# raspdancer11_1_0.net
KiCad netlist of a schematic drawn in EAGLE
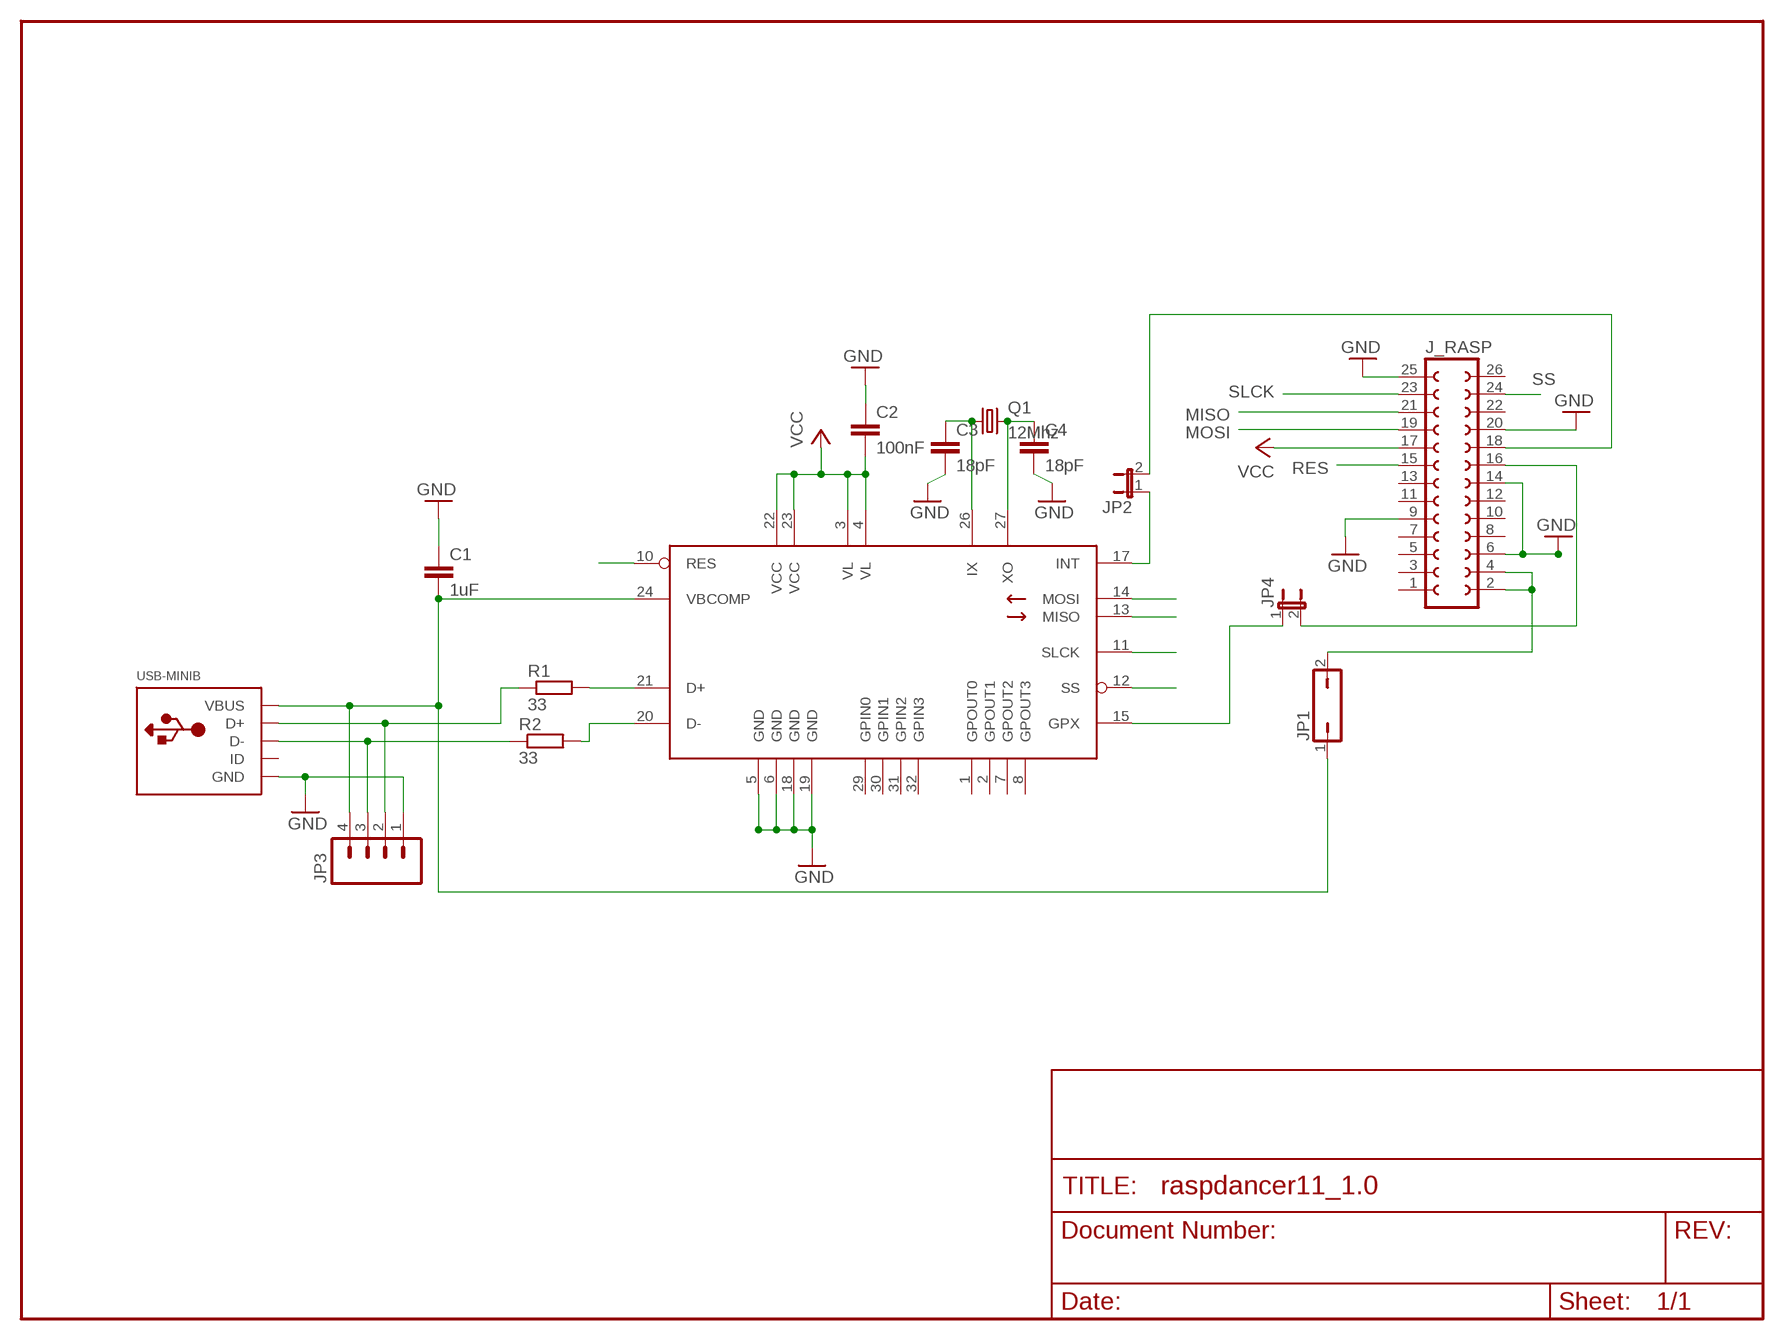
[diagram p0: schematic, sheet 1]

(export (version "E")
  (design (tool "Eeschema 10.0.6"))
  (components
    (comp (ref "C1")
      (value "1uF")
      (footprint "eagle-import:C1206")
      (libsource (lib "eagle-import") (part "C1206"))
    )
    (comp (ref "C2")
      (value "100nF")
      (footprint "eagle-import:C1206")
      (libsource (lib "eagle-import") (part "C1206"))
    )
    (comp (ref "C3")
      (value "18pF")
      (footprint "eagle-import:C1206")
      (libsource (lib "eagle-import") (part "C1206"))
    )
    (comp (ref "C4")
      (value "18pF")
      (footprint "eagle-import:C1206")
      (libsource (lib "eagle-import") (part "C1206"))
    )
    (comp (ref "JP1")
      (value "JP1Q")
      (footprint "eagle-import:JP1")
      (libsource (lib "eagle-import") (part "JP1Q"))
    )
    (comp (ref "JP2")
      (value "JUMPER-2-OLDSMD-NO")
      (footprint "eagle-import:SJ_2S-NO")
      (libsource (lib "eagle-import") (part "JUMPER-2-OLDSMD-NO"))
    )
    (comp (ref "JP3")
      (value "M04PTH")
      (footprint "eagle-import:1X04")
      (libsource (lib "eagle-import") (part "M04PTH"))
    )
    (comp (ref "JP4")
      (value "JUMPER-2-OLDSMD-NO")
      (footprint "eagle-import:SJ_2S-NO")
      (libsource (lib "eagle-import") (part "JUMPER-2-OLDSMD-NO"))
    )
    (comp (ref "J_RASP")
      (value "FE13-2")
      (footprint "eagle-import:FE13-2")
      (libsource (lib "eagle-import") (part "FE13-2"))
    )
    (comp (ref "Q1")
      (value "12Mhz")
      (footprint "eagle-import:CTS406")
      (libsource (lib "eagle-import") (part "CRYSTALCTS406"))
    )
    (comp (ref "R1")
      (value "33")
      (footprint "eagle-import:R1206")
      (libsource (lib "eagle-import") (part "R1206"))
    )
    (comp (ref "R2")
      (value "33")
      (footprint "eagle-import:R1206")
      (libsource (lib "eagle-import") (part "R1206"))
    )
    (comp (ref "U1")
      (value "MAX3420")
      (footprint "eagle-import:TQFP32-08")
      (libsource (lib "eagle-import") (part "MAX3420"))
    )
    (comp (ref "USB-MINIB")
      (value "USBMINIB")
      (footprint "eagle-import:USB-MINIB")
      (libsource (lib "eagle-import") (part "USBMINIB"))
    )
  )
  (nets
    (net (code "1") (name "/MISO") (class "Default")
      (node (ref "J_RASP") (pin "21") (pinfunction "21_21") (pintype "passive"))
      (node (ref "U1") (pin "13") (pinfunction "MISO_13") (pintype "bidirectional"))
    )
    (net (code "2") (name "/MOSI") (class "Default")
      (node (ref "J_RASP") (pin "19") (pinfunction "19_19") (pintype "passive"))
      (node (ref "U1") (pin "14") (pinfunction "MOSI_14") (pintype "bidirectional"))
    )
    (net (code "3") (name "/RES") (class "Default")
      (node (ref "J_RASP") (pin "15") (pinfunction "15_15") (pintype "passive"))
      (node (ref "U1") (pin "10") (pinfunction "RES_10") (pintype "bidirectional"))
    )
    (net (code "4") (name "/SLCK") (class "Default")
      (node (ref "J_RASP") (pin "23") (pinfunction "23_23") (pintype "passive"))
      (node (ref "U1") (pin "11") (pinfunction "SLCK_11") (pintype "bidirectional"))
    )
    (net (code "5") (name "/SS") (class "Default")
      (node (ref "J_RASP") (pin "24") (pinfunction "24_24") (pintype "passive"))
      (node (ref "U1") (pin "12") (pinfunction "SS_12") (pintype "bidirectional"))
    )
    (net (code "6") (name "GND") (class "Default")
      (node (ref "C1") (pin "1") (pinfunction "1_1") (pintype "passive"))
      (node (ref "C2") (pin "1") (pinfunction "1_1") (pintype "passive"))
      (node (ref "C3") (pin "2") (pinfunction "2_2") (pintype "passive"))
      (node (ref "C4") (pin "2") (pinfunction "2_2") (pintype "passive"))
      (node (ref "JP3") (pin "1") (pinfunction "1_1") (pintype "passive"))
      (node (ref "J_RASP") (pin "14") (pinfunction "14_14") (pintype "passive"))
      (node (ref "J_RASP") (pin "20") (pinfunction "20_20") (pintype "passive"))
      (node (ref "J_RASP") (pin "25") (pinfunction "25_25") (pintype "passive"))
      (node (ref "J_RASP") (pin "6") (pinfunction "6_6") (pintype "passive"))
      (node (ref "J_RASP") (pin "9") (pinfunction "9_9") (pintype "passive"))
      (node (ref "U1") (pin "18") (pinfunction "GND_18") (pintype "bidirectional"))
      (node (ref "U1") (pin "19") (pinfunction "GND_19") (pintype "bidirectional"))
      (node (ref "U1") (pin "5") (pinfunction "GND_5") (pintype "bidirectional"))
      (node (ref "U1") (pin "6") (pinfunction "GND_6") (pintype "bidirectional"))
      (node (ref "USB-MINIB") (pin "GND") (pinfunction "GND_GND") (pintype "power_in"))
    )
    (net (code "7") (name "Net-(JP1-Pad2)") (class "Default")
      (node (ref "JP1") (pin "2") (pinfunction "2_2") (pintype "passive"))
      (node (ref "J_RASP") (pin "2") (pinfunction "2_2") (pintype "passive"))
      (node (ref "J_RASP") (pin "4") (pinfunction "4_4") (pintype "passive"))
    )
    (net (code "8") (name "Net-(JP2-Pad2)") (class "Default")
      (node (ref "JP2") (pin "2") (pinfunction "2_2") (pintype "passive"))
      (node (ref "J_RASP") (pin "18") (pinfunction "18_18") (pintype "passive"))
    )
    (net (code "9") (name "Net-(JP3-Pad2)") (class "Default")
      (node (ref "JP3") (pin "2") (pinfunction "2_2") (pintype "passive"))
      (node (ref "R1") (pin "1") (pinfunction "1_1") (pintype "passive"))
      (node (ref "USB-MINIB") (pin "D+") (pinfunction "D+_D+") (pintype "bidirectional"))
    )
    (net (code "10") (name "Net-(JP3-Pad3)") (class "Default")
      (node (ref "JP3") (pin "3") (pinfunction "3_3") (pintype "passive"))
      (node (ref "R2") (pin "1") (pinfunction "1_1") (pintype "passive"))
      (node (ref "USB-MINIB") (pin "D-") (pinfunction "D-_D-") (pintype "bidirectional"))
    )
    (net (code "11") (name "Net-(JP4-Pad2)") (class "Default")
      (node (ref "JP4") (pin "2") (pinfunction "2_2") (pintype "passive"))
      (node (ref "J_RASP") (pin "16") (pinfunction "16_16") (pintype "passive"))
    )
    (net (code "12") (name "Net-(Q1-2)") (class "Default")
      (node (ref "C4") (pin "1") (pinfunction "1_1") (pintype "passive"))
      (node (ref "Q1") (pin "3") (pinfunction "2_3") (pintype "passive"))
      (node (ref "U1") (pin "27") (pinfunction "XO_27") (pintype "bidirectional"))
    )
    (net (code "13") (name "Net-(U1-D+)") (class "Default")
      (node (ref "R1") (pin "2") (pinfunction "2_2") (pintype "passive"))
      (node (ref "U1") (pin "21") (pinfunction "D+_21") (pintype "bidirectional"))
    )
    (net (code "14") (name "Net-(U1-D-)") (class "Default")
      (node (ref "R2") (pin "2") (pinfunction "2_2") (pintype "passive"))
      (node (ref "U1") (pin "20") (pinfunction "D-_20") (pintype "bidirectional"))
    )
    (net (code "15") (name "Net-(U1-GPX)") (class "Default")
      (node (ref "JP4") (pin "1") (pinfunction "1_1") (pintype "passive"))
      (node (ref "U1") (pin "15") (pinfunction "GPX_15") (pintype "bidirectional"))
    )
    (net (code "16") (name "Net-(U1-INT)") (class "Default")
      (node (ref "JP2") (pin "1") (pinfunction "1_1") (pintype "passive"))
      (node (ref "U1") (pin "17") (pinfunction "INT_17") (pintype "bidirectional"))
    )
    (net (code "17") (name "Net-(U1-IX)") (class "Default")
      (node (ref "C3") (pin "1") (pinfunction "1_1") (pintype "passive"))
      (node (ref "Q1") (pin "1") (pinfunction "1_1") (pintype "passive"))
      (node (ref "U1") (pin "26") (pinfunction "IX_26") (pintype "bidirectional"))
    )
    (net (code "18") (name "Net-(U1-VBCOMP)") (class "Default")
      (node (ref "C1") (pin "2") (pinfunction "2_2") (pintype "passive"))
      (node (ref "JP1") (pin "1") (pinfunction "1_1") (pintype "passive"))
      (node (ref "JP3") (pin "4") (pinfunction "4_4") (pintype "passive"))
      (node (ref "U1") (pin "24") (pinfunction "VBCOMP_24") (pintype "bidirectional"))
      (node (ref "USB-MINIB") (pin "VBUS") (pinfunction "VBUS_VBUS") (pintype "power_in"))
    )
    (net (code "19") (name "VCC") (class "Default")
      (node (ref "C2") (pin "2") (pinfunction "2_2") (pintype "passive"))
      (node (ref "J_RASP") (pin "17") (pinfunction "17_17") (pintype "passive"))
      (node (ref "U1") (pin "22") (pinfunction "VCC_22") (pintype "bidirectional"))
      (node (ref "U1") (pin "23") (pinfunction "VCC_23") (pintype "bidirectional"))
      (node (ref "U1") (pin "3") (pinfunction "VL_3") (pintype "bidirectional"))
      (node (ref "U1") (pin "4") (pinfunction "VL_4") (pintype "bidirectional"))
    )
    (net (code "20") (name "unconnected-(J_RASP-Pad1)") (class "Default")
      (node (ref "J_RASP") (pin "1") (pinfunction "1_1") (pintype "passive"))
    )
    (net (code "21") (name "unconnected-(J_RASP-Pad3)") (class "Default")
      (node (ref "J_RASP") (pin "3") (pinfunction "3_3") (pintype "passive"))
    )
    (net (code "22") (name "unconnected-(J_RASP-Pad5)") (class "Default")
      (node (ref "J_RASP") (pin "5") (pinfunction "5_5") (pintype "passive"))
    )
    (net (code "23") (name "unconnected-(J_RASP-Pad7)") (class "Default")
      (node (ref "J_RASP") (pin "7") (pinfunction "7_7") (pintype "passive"))
    )
    (net (code "24") (name "unconnected-(J_RASP-Pad8)") (class "Default")
      (node (ref "J_RASP") (pin "8") (pinfunction "8_8") (pintype "passive"))
    )
    (net (code "25") (name "unconnected-(J_RASP-Pad10)") (class "Default")
      (node (ref "J_RASP") (pin "10") (pinfunction "10_10") (pintype "passive"))
    )
    (net (code "26") (name "unconnected-(J_RASP-Pad11)") (class "Default")
      (node (ref "J_RASP") (pin "11") (pinfunction "11_11") (pintype "passive"))
    )
    (net (code "27") (name "unconnected-(J_RASP-Pad12)") (class "Default")
      (node (ref "J_RASP") (pin "12") (pinfunction "12_12") (pintype "passive"))
    )
    (net (code "28") (name "unconnected-(J_RASP-Pad13)") (class "Default")
      (node (ref "J_RASP") (pin "13") (pinfunction "13_13") (pintype "passive"))
    )
    (net (code "29") (name "unconnected-(J_RASP-Pad22)") (class "Default")
      (node (ref "J_RASP") (pin "22") (pinfunction "22_22") (pintype "passive"))
    )
    (net (code "30") (name "unconnected-(J_RASP-Pad26)") (class "Default")
      (node (ref "J_RASP") (pin "26") (pinfunction "26_26") (pintype "passive"))
    )
    (net (code "31") (name "unconnected-(U1-GPIN0-Pad29)") (class "Default")
      (node (ref "U1") (pin "29") (pinfunction "GPIN0_29") (pintype "bidirectional"))
    )
    (net (code "32") (name "unconnected-(U1-GPIN1-Pad30)") (class "Default")
      (node (ref "U1") (pin "30") (pinfunction "GPIN1_30") (pintype "bidirectional"))
    )
    (net (code "33") (name "unconnected-(U1-GPIN2-Pad31)") (class "Default")
      (node (ref "U1") (pin "31") (pinfunction "GPIN2_31") (pintype "bidirectional"))
    )
    (net (code "34") (name "unconnected-(U1-GPIN3-Pad32)") (class "Default")
      (node (ref "U1") (pin "32") (pinfunction "GPIN3_32") (pintype "bidirectional"))
    )
    (net (code "35") (name "unconnected-(U1-GPOUT0-Pad1)") (class "Default")
      (node (ref "U1") (pin "1") (pinfunction "GPOUT0_1") (pintype "bidirectional"))
    )
    (net (code "36") (name "unconnected-(U1-GPOUT1-Pad2)") (class "Default")
      (node (ref "U1") (pin "2") (pinfunction "GPOUT1_2") (pintype "bidirectional"))
    )
    (net (code "37") (name "unconnected-(U1-GPOUT2-Pad7)") (class "Default")
      (node (ref "U1") (pin "7") (pinfunction "GPOUT2_7") (pintype "bidirectional"))
    )
    (net (code "38") (name "unconnected-(U1-GPOUT3-Pad8)") (class "Default")
      (node (ref "U1") (pin "8") (pinfunction "GPOUT3_8") (pintype "bidirectional"))
    )
    (net (code "39") (name "unconnected-(USB-MINIB-PadID)") (class "Default")
      (node (ref "USB-MINIB") (pin "ID") (pinfunction "ID_ID") (pintype "bidirectional"))
    )
  )
)
